# fb_relais_8_230V_85a.net
KiCad netlist of a schematic drawn in EAGLE
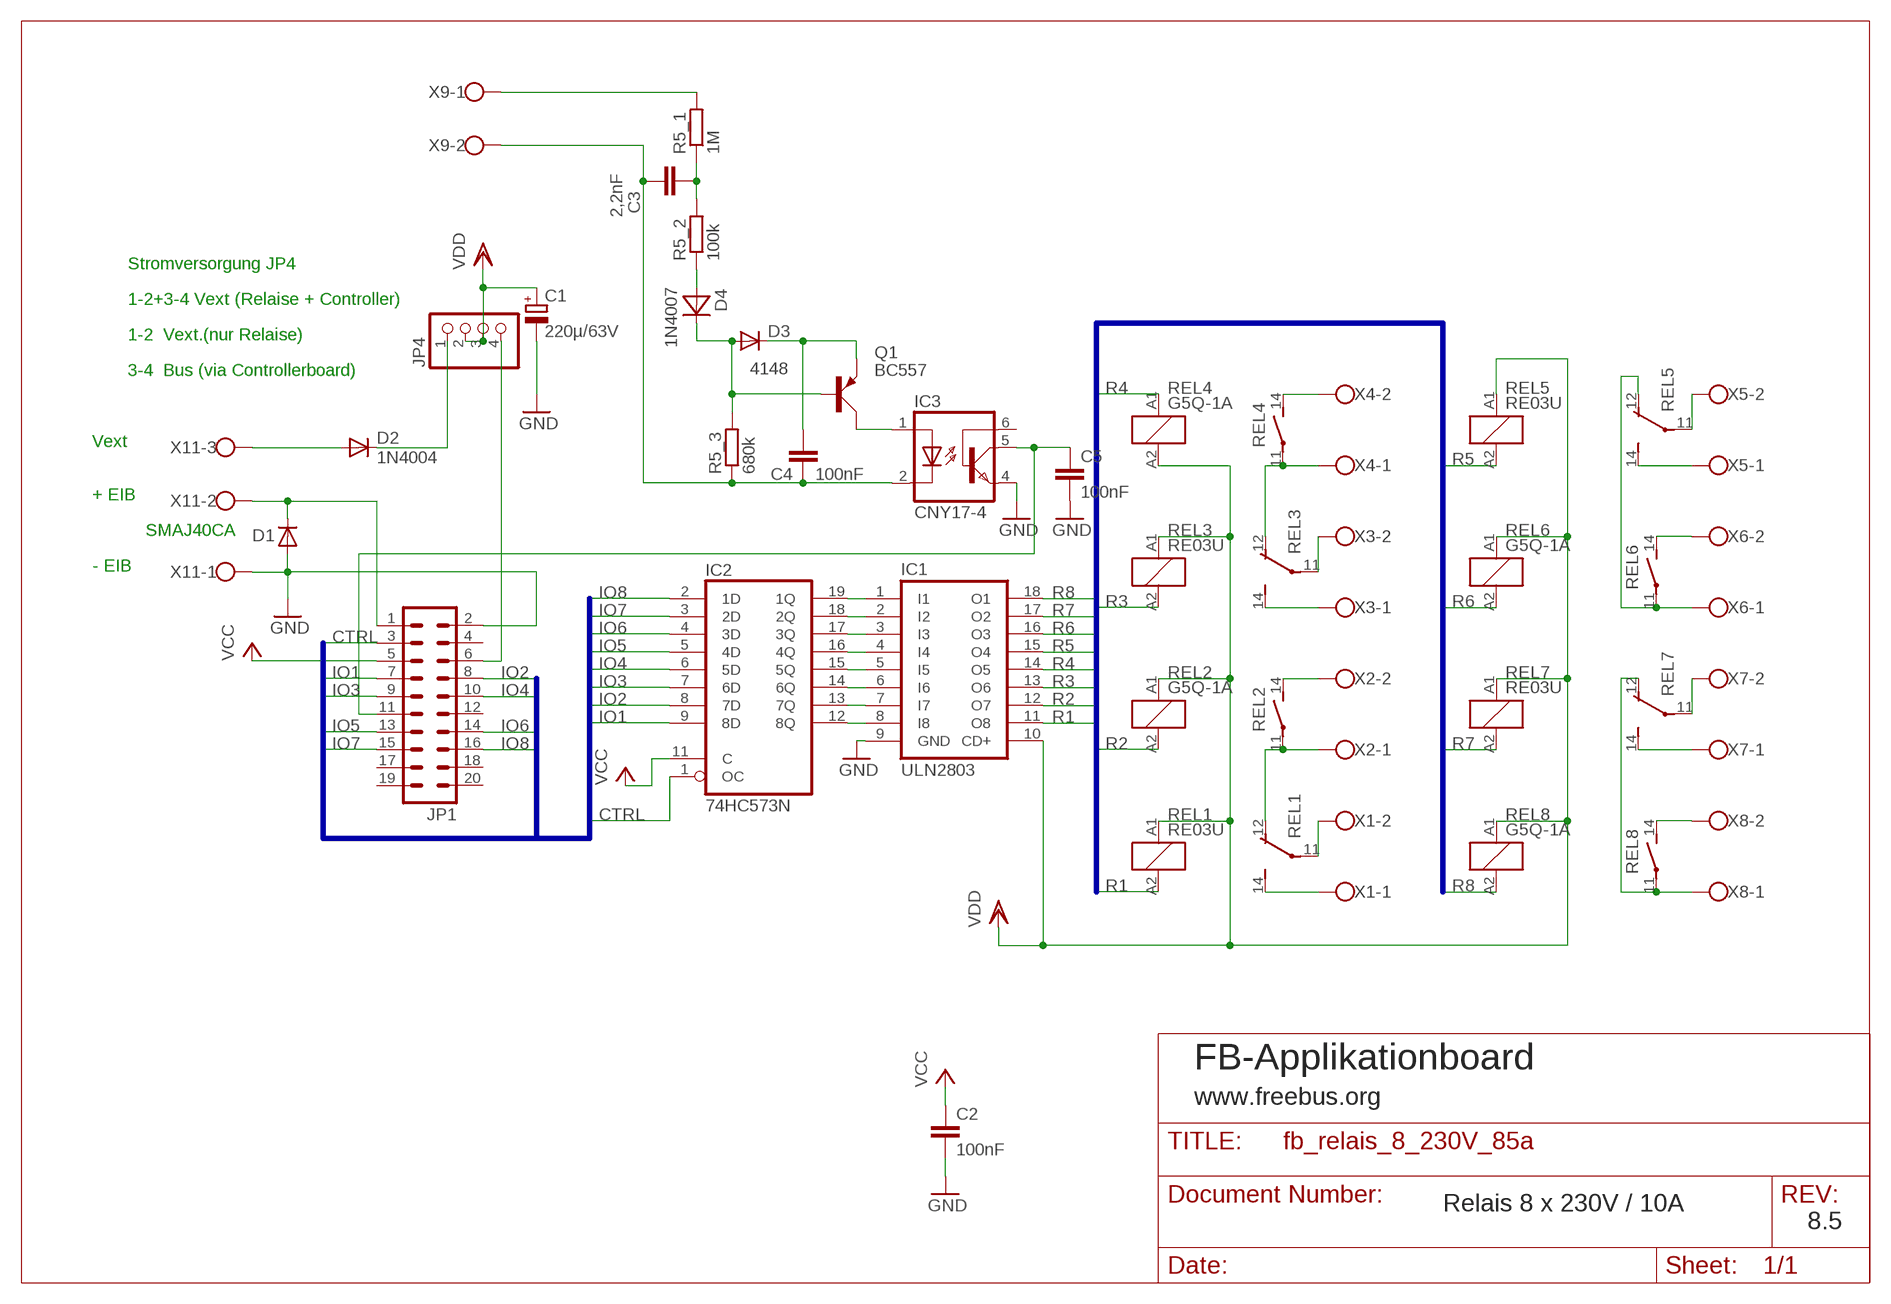
[diagram p0: schematic, sheet 1]

(export (version "E")
  (design (tool "Eeschema 10.0.6"))
  (components
    (comp (ref "C1")
      (value "220µ/63V")
      (footprint "eagle-import:E5-10,5")
      (libsource (lib "eagle-import") (part "CPOL-EUE5-10.5"))
    )
    (comp (ref "C2")
      (value "100nF")
      (footprint "eagle-import:C050-024X044")
      (libsource (lib "eagle-import") (part "C-EU050-024X044"))
    )
    (comp (ref "C3")
      (value "2,2nF")
      (footprint "eagle-import:C102-043X133")
      (libsource (lib "eagle-import") (part "C-EU102-043X133"))
    )
    (comp (ref "C4")
      (value "100nF")
      (footprint "eagle-import:C050-024X044")
      (libsource (lib "eagle-import") (part "C-EU050-024X044"))
    )
    (comp (ref "C5")
      (value "100nF")
      (footprint "eagle-import:C050-024X044")
      (libsource (lib "eagle-import") (part "C-EU050-024X044"))
    )
    (comp (ref "D1")
      (value "D-SMB")
      (footprint "eagle-import:SMB")
      (libsource (lib "eagle-import") (part "D-SMB"))
    )
    (comp (ref "D2")
      (value "1N4004")
      (footprint "eagle-import:DO41-10")
      (libsource (lib "eagle-import") (part "1N4004"))
    )
    (comp (ref "D3")
      (value "4148")
      (footprint "eagle-import:D-2.5")
      (libsource (lib "eagle-import") (part "1N41481448V"))
    )
    (comp (ref "D4")
      (value "1N4007")
      (footprint "eagle-import:DO41-7")
      (libsource (lib "eagle-import") (part "1N4007"))
    )
    (comp (ref "IC1")
      (value "ULN2803")
      (footprint "eagle-import:DIL18")
      (libsource (lib "eagle-import") (part "ULN2803A"))
    )
    (comp (ref "IC2")
      (value "74HC573N")
      (footprint "eagle-import:DIL20")
      (libsource (lib "eagle-import") (part "74573NHC"))
    )
    (comp (ref "IC3")
      (value "CNY17-4")
      (footprint "eagle-import:DIL06")
      (libsource (lib "eagle-import") (part "CNY17"))
    )
    (comp (ref "JP1")
      (value "ML20")
      (footprint "eagle-import:ML20")
      (libsource (lib "eagle-import") (part "ML20"))
    )
    (comp (ref "JP4")
      (value "PINHD-1X4")
      (footprint "eagle-import:1X04")
      (libsource (lib "eagle-import") (part "PINHD-1X4"))
    )
    (comp (ref "Q1")
      (value "BC557")
      (footprint "eagle-import:SOT54A")
      (libsource (lib "eagle-import") (part "BC557"))
    )
    (comp (ref "R5_1")
      (value "1M")
      (footprint "eagle-import:0207_7")
      (libsource (lib "eagle-import") (part "R-EU_0207/7"))
    )
    (comp (ref "R5_2")
      (value "100k")
      (footprint "eagle-import:0207_7")
      (libsource (lib "eagle-import") (part "R-EU_0207/7"))
    )
    (comp (ref "R5_3")
      (value "680k")
      (footprint "eagle-import:0207_7")
      (libsource (lib "eagle-import") (part "R-EU_0207/7"))
    )
    (comp (ref "REL1")
      (value "RE03U")
      (footprint "eagle-import:G5Q_1_EU")
      (libsource (lib "eagle-import") (part "RE03U"))
    )
    (comp (ref "REL2")
      (value "G5Q-1A")
      (footprint "eagle-import:RE-SCHRACK")
      (libsource (lib "eagle-import") (part "RE030024"))
    )
    (comp (ref "REL3")
      (value "RE03U")
      (footprint "eagle-import:G5Q_1_EU")
      (libsource (lib "eagle-import") (part "RE03U"))
    )
    (comp (ref "REL4")
      (value "G5Q-1A")
      (footprint "eagle-import:RE-SCHRACK")
      (libsource (lib "eagle-import") (part "RE030024"))
    )
    (comp (ref "REL5")
      (value "RE03U")
      (footprint "eagle-import:G5Q_1_EU")
      (libsource (lib "eagle-import") (part "RE03U"))
    )
    (comp (ref "REL6")
      (value "G5Q-1A")
      (footprint "eagle-import:RE-SCHRACK")
      (libsource (lib "eagle-import") (part "RE030024"))
    )
    (comp (ref "REL7")
      (value "RE03U")
      (footprint "eagle-import:G5Q_1_EU")
      (libsource (lib "eagle-import") (part "RE03U"))
    )
    (comp (ref "REL8")
      (value "G5Q-1A")
      (footprint "eagle-import:RE-SCHRACK")
      (libsource (lib "eagle-import") (part "RE030024"))
    )
    (comp (ref "X1")
      (value "W237-102")
      (footprint "eagle-import:W237-102")
      (libsource (lib "eagle-import") (part "W237-102"))
    )
    (comp (ref "X2")
      (value "W237-102")
      (footprint "eagle-import:W237-102")
      (libsource (lib "eagle-import") (part "W237-102"))
    )
    (comp (ref "X3")
      (value "W237-102")
      (footprint "eagle-import:W237-102")
      (libsource (lib "eagle-import") (part "W237-102"))
    )
    (comp (ref "X4")
      (value "W237-102")
      (footprint "eagle-import:W237-102")
      (libsource (lib "eagle-import") (part "W237-102"))
    )
    (comp (ref "X5")
      (value "W237-102")
      (footprint "eagle-import:W237-102")
      (libsource (lib "eagle-import") (part "W237-102"))
    )
    (comp (ref "X6")
      (value "W237-102")
      (footprint "eagle-import:W237-102")
      (libsource (lib "eagle-import") (part "W237-102"))
    )
    (comp (ref "X7")
      (value "W237-102")
      (footprint "eagle-import:W237-102")
      (libsource (lib "eagle-import") (part "W237-102"))
    )
    (comp (ref "X8")
      (value "W237-102")
      (footprint "eagle-import:W237-102")
      (libsource (lib "eagle-import") (part "W237-102"))
    )
    (comp (ref "X9")
      (value "W237-102")
      (footprint "eagle-import:W237-102")
      (libsource (lib "eagle-import") (part "W237-102"))
    )
    (comp (ref "X11")
      (value "W237-3E")
      (footprint "eagle-import:W237-3E")
      (libsource (lib "eagle-import") (part "W237-3E"))
    )
  )
  (nets
    (net (code "1") (name "/CTRL") (class "Default")
      (node (ref "IC2") (pin "1") (pinfunction "OC_1") (pintype "input"))
      (node (ref "JP1") (pin "3") (pinfunction "3_3") (pintype "passive"))
    )
    (net (code "2") (name "/IO1") (class "Default")
      (node (ref "IC2") (pin "9") (pinfunction "8D_9") (pintype "input"))
      (node (ref "JP1") (pin "7") (pinfunction "7_7") (pintype "passive"))
    )
    (net (code "3") (name "/IO2") (class "Default")
      (node (ref "IC2") (pin "8") (pinfunction "7D_8") (pintype "input"))
      (node (ref "JP1") (pin "8") (pinfunction "8_8") (pintype "passive"))
    )
    (net (code "4") (name "/IO3") (class "Default")
      (node (ref "IC2") (pin "7") (pinfunction "6D_7") (pintype "input"))
      (node (ref "JP1") (pin "9") (pinfunction "9_9") (pintype "passive"))
    )
    (net (code "5") (name "/IO4") (class "Default")
      (node (ref "IC2") (pin "6") (pinfunction "5D_6") (pintype "input"))
      (node (ref "JP1") (pin "10") (pinfunction "10_10") (pintype "passive"))
    )
    (net (code "6") (name "/IO5") (class "Default")
      (node (ref "IC2") (pin "5") (pinfunction "4D_5") (pintype "input"))
      (node (ref "JP1") (pin "13") (pinfunction "13_13") (pintype "passive"))
    )
    (net (code "7") (name "/IO6") (class "Default")
      (node (ref "IC2") (pin "4") (pinfunction "3D_4") (pintype "input"))
      (node (ref "JP1") (pin "14") (pinfunction "14_14") (pintype "passive"))
    )
    (net (code "8") (name "/IO7") (class "Default")
      (node (ref "IC2") (pin "3") (pinfunction "2D_3") (pintype "input"))
      (node (ref "JP1") (pin "15") (pinfunction "15_15") (pintype "passive"))
    )
    (net (code "9") (name "/IO8") (class "Default")
      (node (ref "IC2") (pin "2") (pinfunction "1D_2") (pintype "input"))
      (node (ref "JP1") (pin "16") (pinfunction "16_16") (pintype "passive"))
    )
    (net (code "10") (name "/R1") (class "Default")
      (node (ref "IC1") (pin "11") (pinfunction "O8_11") (pintype "open_collector"))
      (node (ref "REL1") (pin "A2") (pinfunction "2_A2") (pintype "passive"))
    )
    (net (code "11") (name "/R2") (class "Default")
      (node (ref "IC1") (pin "12") (pinfunction "O7_12") (pintype "open_collector"))
      (node (ref "REL2") (pin "A2") (pinfunction "2_A2") (pintype "passive"))
    )
    (net (code "12") (name "/R3") (class "Default")
      (node (ref "IC1") (pin "13") (pinfunction "O6_13") (pintype "open_collector"))
      (node (ref "REL3") (pin "A2") (pinfunction "2_A2") (pintype "passive"))
    )
    (net (code "13") (name "/R4") (class "Default")
      (node (ref "IC1") (pin "14") (pinfunction "O5_14") (pintype "open_collector"))
      (node (ref "REL4") (pin "A1") (pinfunction "1_A1") (pintype "passive"))
    )
    (net (code "14") (name "/R5") (class "Default")
      (node (ref "IC1") (pin "15") (pinfunction "O4_15") (pintype "open_collector"))
      (node (ref "REL5") (pin "A2") (pinfunction "2_A2") (pintype "passive"))
    )
    (net (code "15") (name "/R6") (class "Default")
      (node (ref "IC1") (pin "16") (pinfunction "O3_16") (pintype "open_collector"))
      (node (ref "REL6") (pin "A2") (pinfunction "2_A2") (pintype "passive"))
    )
    (net (code "16") (name "/R7") (class "Default")
      (node (ref "IC1") (pin "17") (pinfunction "O2_17") (pintype "open_collector"))
      (node (ref "REL7") (pin "A2") (pinfunction "2_A2") (pintype "passive"))
    )
    (net (code "17") (name "/R8") (class "Default")
      (node (ref "IC1") (pin "18") (pinfunction "O1_18") (pintype "open_collector"))
      (node (ref "REL8") (pin "A2") (pinfunction "2_A2") (pintype "passive"))
    )
    (net (code "18") (name "GND") (class "Default")
      (node (ref "C1") (pin "-") (pinfunction "-_-") (pintype "passive"))
      (node (ref "C2") (pin "2") (pinfunction "2_2") (pintype "passive"))
      (node (ref "C5") (pin "2") (pinfunction "2_2") (pintype "passive"))
      (node (ref "D1") (pin "2") (pinfunction "A_2") (pintype "passive"))
      (node (ref "IC1") (pin "9") (pinfunction "GND_9") (pintype "power_in"))
      (node (ref "IC3") (pin "4") (pinfunction "EMI_4") (pintype "passive"))
      (node (ref "JP1") (pin "2") (pinfunction "2_2") (pintype "passive"))
      (node (ref "X11") (pin "1") (pinfunction "KL_1") (pintype "passive"))
    )
    (net (code "19") (name "Net-(C3-Pad1)") (class "Default")
      (node (ref "C3") (pin "1") (pinfunction "1_1") (pintype "passive"))
      (node (ref "R5_1") (pin "1") (pinfunction "1_1") (pintype "passive"))
      (node (ref "R5_2") (pin "2") (pinfunction "2_2") (pintype "passive"))
    )
    (net (code "20") (name "Net-(C4-Pad2)") (class "Default")
      (node (ref "C4") (pin "2") (pinfunction "2_2") (pintype "passive"))
      (node (ref "D3") (pin "C") (pinfunction "C_C") (pintype "passive"))
      (node (ref "Q1") (pin "E") (pinfunction "E_E") (pintype "passive"))
    )
    (net (code "21") (name "Net-(D1-C)") (class "Default")
      (node (ref "D1") (pin "1") (pinfunction "C_1") (pintype "passive"))
      (node (ref "JP1") (pin "1") (pinfunction "1_1") (pintype "passive"))
      (node (ref "X11") (pin "2") (pinfunction "KL_2") (pintype "passive"))
    )
    (net (code "22") (name "Net-(D2-PadC)") (class "Default")
      (node (ref "D2") (pin "C") (pinfunction "C_C") (pintype "passive"))
      (node (ref "JP4") (pin "1") (pinfunction "1_1") (pintype "passive"))
    )
    (net (code "23") (name "Net-(D3-PadA)") (class "Default")
      (node (ref "D3") (pin "A") (pinfunction "A_A") (pintype "passive"))
      (node (ref "D4") (pin "C") (pinfunction "C_C") (pintype "passive"))
      (node (ref "Q1") (pin "B") (pinfunction "B_B") (pintype "passive"))
      (node (ref "R5_3") (pin "2") (pinfunction "2_2") (pintype "passive"))
    )
    (net (code "24") (name "Net-(D4-PadA)") (class "Default")
      (node (ref "D4") (pin "A") (pinfunction "A_A") (pintype "passive"))
      (node (ref "R5_2") (pin "1") (pinfunction "1_1") (pintype "passive"))
    )
    (net (code "25") (name "Net-(IC1-I1)") (class "Default")
      (node (ref "IC1") (pin "1") (pinfunction "I1_1") (pintype "input"))
      (node (ref "IC2") (pin "19") (pinfunction "1Q_19") (pintype "tri_state"))
    )
    (net (code "26") (name "Net-(IC1-I2)") (class "Default")
      (node (ref "IC1") (pin "2") (pinfunction "I2_2") (pintype "input"))
      (node (ref "IC2") (pin "18") (pinfunction "2Q_18") (pintype "tri_state"))
    )
    (net (code "27") (name "Net-(IC1-I3)") (class "Default")
      (node (ref "IC1") (pin "3") (pinfunction "I3_3") (pintype "input"))
      (node (ref "IC2") (pin "17") (pinfunction "3Q_17") (pintype "tri_state"))
    )
    (net (code "28") (name "Net-(IC1-I4)") (class "Default")
      (node (ref "IC1") (pin "4") (pinfunction "I4_4") (pintype "input"))
      (node (ref "IC2") (pin "16") (pinfunction "4Q_16") (pintype "tri_state"))
    )
    (net (code "29") (name "Net-(IC1-I5)") (class "Default")
      (node (ref "IC1") (pin "5") (pinfunction "I5_5") (pintype "input"))
      (node (ref "IC2") (pin "15") (pinfunction "5Q_15") (pintype "tri_state"))
    )
    (net (code "30") (name "Net-(IC1-I6)") (class "Default")
      (node (ref "IC1") (pin "6") (pinfunction "I6_6") (pintype "input"))
      (node (ref "IC2") (pin "14") (pinfunction "6Q_14") (pintype "tri_state"))
    )
    (net (code "31") (name "Net-(IC1-I7)") (class "Default")
      (node (ref "IC1") (pin "7") (pinfunction "I7_7") (pintype "input"))
      (node (ref "IC2") (pin "13") (pinfunction "7Q_13") (pintype "tri_state"))
    )
    (net (code "32") (name "Net-(IC1-I8)") (class "Default")
      (node (ref "IC1") (pin "8") (pinfunction "I8_8") (pintype "input"))
      (node (ref "IC2") (pin "12") (pinfunction "8Q_12") (pintype "tri_state"))
    )
    (net (code "33") (name "Net-(IC3-A)") (class "Default")
      (node (ref "IC3") (pin "1") (pinfunction "A_1") (pintype "passive"))
      (node (ref "Q1") (pin "C") (pinfunction "C_C") (pintype "passive"))
    )
    (net (code "34") (name "Net-(IC3-C)") (class "Default")
      (node (ref "C3") (pin "2") (pinfunction "2_2") (pintype "passive"))
      (node (ref "C4") (pin "1") (pinfunction "1_1") (pintype "passive"))
      (node (ref "IC3") (pin "2") (pinfunction "C_2") (pintype "passive"))
      (node (ref "R5_3") (pin "1") (pinfunction "1_1") (pintype "passive"))
      (node (ref "X9") (pin "2") (pinfunction "KL_2") (pintype "passive"))
    )
    (net (code "35") (name "Net-(IC3-COL)") (class "Default")
      (node (ref "C5") (pin "1") (pinfunction "1_1") (pintype "passive"))
      (node (ref "IC3") (pin "5") (pinfunction "COL_5") (pintype "passive"))
      (node (ref "JP1") (pin "11") (pinfunction "11_11") (pintype "passive"))
    )
    (net (code "36") (name "Net-(JP1-Pad6)") (class "Default")
      (node (ref "JP1") (pin "6") (pinfunction "6_6") (pintype "passive"))
      (node (ref "JP4") (pin "4") (pinfunction "4_4") (pintype "passive"))
    )
    (net (code "37") (name "Net-(REL1A-O)") (class "Default")
      (node (ref "REL1") (pin "12") (pinfunction "O_12") (pintype "passive"))
      (node (ref "REL2") (pin "11") (pinfunction "P_11") (pintype "passive"))
      (node (ref "X2") (pin "1") (pinfunction "KL_1") (pintype "passive"))
    )
    (net (code "38") (name "Net-(REL1A-P)") (class "Default")
      (node (ref "REL1") (pin "11") (pinfunction "P_11") (pintype "passive"))
      (node (ref "X1") (pin "2") (pinfunction "KL_2") (pintype "passive"))
    )
    (net (code "39") (name "Net-(REL1A-S)") (class "Default")
      (node (ref "REL1") (pin "14") (pinfunction "S_14") (pintype "passive"))
      (node (ref "X1") (pin "1") (pinfunction "KL_1") (pintype "passive"))
    )
    (net (code "40") (name "Net-(REL2B-S)") (class "Default")
      (node (ref "REL2") (pin "14") (pinfunction "S_14") (pintype "passive"))
      (node (ref "X2") (pin "2") (pinfunction "KL_2") (pintype "passive"))
    )
    (net (code "41") (name "Net-(REL3A-O)") (class "Default")
      (node (ref "REL3") (pin "12") (pinfunction "O_12") (pintype "passive"))
      (node (ref "REL4") (pin "11") (pinfunction "P_11") (pintype "passive"))
      (node (ref "X4") (pin "1") (pinfunction "KL_1") (pintype "passive"))
    )
    (net (code "42") (name "Net-(REL3A-P)") (class "Default")
      (node (ref "REL3") (pin "11") (pinfunction "P_11") (pintype "passive"))
      (node (ref "X3") (pin "2") (pinfunction "KL_2") (pintype "passive"))
    )
    (net (code "43") (name "Net-(REL3A-S)") (class "Default")
      (node (ref "REL3") (pin "14") (pinfunction "S_14") (pintype "passive"))
      (node (ref "X3") (pin "1") (pinfunction "KL_1") (pintype "passive"))
    )
    (net (code "44") (name "Net-(REL4B-S)") (class "Default")
      (node (ref "REL4") (pin "14") (pinfunction "S_14") (pintype "passive"))
      (node (ref "X4") (pin "2") (pinfunction "KL_2") (pintype "passive"))
    )
    (net (code "45") (name "Net-(REL5A-O)") (class "Default")
      (node (ref "REL5") (pin "12") (pinfunction "O_12") (pintype "passive"))
      (node (ref "REL6") (pin "11") (pinfunction "P_11") (pintype "passive"))
      (node (ref "X6") (pin "1") (pinfunction "KL_1") (pintype "passive"))
    )
    (net (code "46") (name "Net-(REL5A-P)") (class "Default")
      (node (ref "REL5") (pin "11") (pinfunction "P_11") (pintype "passive"))
      (node (ref "X5") (pin "2") (pinfunction "KL_2") (pintype "passive"))
    )
    (net (code "47") (name "Net-(REL5A-S)") (class "Default")
      (node (ref "REL5") (pin "14") (pinfunction "S_14") (pintype "passive"))
      (node (ref "X5") (pin "1") (pinfunction "KL_1") (pintype "passive"))
    )
    (net (code "48") (name "Net-(REL6B-S)") (class "Default")
      (node (ref "REL6") (pin "14") (pinfunction "S_14") (pintype "passive"))
      (node (ref "X6") (pin "2") (pinfunction "KL_2") (pintype "passive"))
    )
    (net (code "49") (name "Net-(REL7A-O)") (class "Default")
      (node (ref "REL7") (pin "12") (pinfunction "O_12") (pintype "passive"))
      (node (ref "REL8") (pin "11") (pinfunction "P_11") (pintype "passive"))
      (node (ref "X8") (pin "1") (pinfunction "KL_1") (pintype "passive"))
    )
    (net (code "50") (name "Net-(REL7A-P)") (class "Default")
      (node (ref "REL7") (pin "11") (pinfunction "P_11") (pintype "passive"))
      (node (ref "X7") (pin "2") (pinfunction "KL_2") (pintype "passive"))
    )
    (net (code "51") (name "Net-(REL7A-S)") (class "Default")
      (node (ref "REL7") (pin "14") (pinfunction "S_14") (pintype "passive"))
      (node (ref "X7") (pin "1") (pinfunction "KL_1") (pintype "passive"))
    )
    (net (code "52") (name "Net-(REL8B-S)") (class "Default")
      (node (ref "REL8") (pin "14") (pinfunction "S_14") (pintype "passive"))
      (node (ref "X8") (pin "2") (pinfunction "KL_2") (pintype "passive"))
    )
    (net (code "53") (name "Net-(X9A-KL)") (class "Default")
      (node (ref "R5_1") (pin "2") (pinfunction "2_2") (pintype "passive"))
      (node (ref "X9") (pin "1") (pinfunction "KL_1") (pintype "passive"))
    )
    (net (code "54") (name "Net-(X11C-KL)") (class "Default")
      (node (ref "D2") (pin "A") (pinfunction "A_A") (pintype "passive"))
      (node (ref "X11") (pin "3") (pinfunction "KL_3") (pintype "passive"))
    )
    (net (code "55") (name "VCC") (class "Default")
      (node (ref "C2") (pin "1") (pinfunction "1_1") (pintype "passive"))
      (node (ref "IC2") (pin "11") (pinfunction "C_11") (pintype "input"))
      (node (ref "JP1") (pin "5") (pinfunction "5_5") (pintype "passive"))
    )
    (net (code "56") (name "VDD") (class "Default")
      (node (ref "C1") (pin "+") (pinfunction "+_+") (pintype "passive"))
      (node (ref "IC1") (pin "10") (pinfunction "CD+_10") (pintype "passive"))
      (node (ref "JP4") (pin "2") (pinfunction "2_2") (pintype "passive"))
      (node (ref "JP4") (pin "3") (pinfunction "3_3") (pintype "passive"))
      (node (ref "REL1") (pin "A1") (pinfunction "1_A1") (pintype "passive"))
      (node (ref "REL2") (pin "A1") (pinfunction "1_A1") (pintype "passive"))
      (node (ref "REL3") (pin "A1") (pinfunction "1_A1") (pintype "passive"))
      (node (ref "REL4") (pin "A2") (pinfunction "2_A2") (pintype "passive"))
      (node (ref "REL5") (pin "A1") (pinfunction "1_A1") (pintype "passive"))
      (node (ref "REL6") (pin "A1") (pinfunction "1_A1") (pintype "passive"))
      (node (ref "REL7") (pin "A1") (pinfunction "1_A1") (pintype "passive"))
      (node (ref "REL8") (pin "A1") (pinfunction "1_A1") (pintype "passive"))
    )
    (net (code "57") (name "unconnected-(IC3-BAS-Pad6)") (class "Default")
      (node (ref "IC3") (pin "6") (pinfunction "BAS_6") (pintype "passive"))
    )
    (net (code "58") (name "unconnected-(JP1-Pad4)") (class "Default")
      (node (ref "JP1") (pin "4") (pinfunction "4_4") (pintype "passive"))
    )
    (net (code "59") (name "unconnected-(JP1-Pad12)") (class "Default")
      (node (ref "JP1") (pin "12") (pinfunction "12_12") (pintype "passive"))
    )
    (net (code "60") (name "unconnected-(JP1-Pad17)") (class "Default")
      (node (ref "JP1") (pin "17") (pinfunction "17_17") (pintype "passive"))
    )
    (net (code "61") (name "unconnected-(JP1-Pad18)") (class "Default")
      (node (ref "JP1") (pin "18") (pinfunction "18_18") (pintype "passive"))
    )
    (net (code "62") (name "unconnected-(JP1-Pad19)") (class "Default")
      (node (ref "JP1") (pin "19") (pinfunction "19_19") (pintype "passive"))
    )
    (net (code "63") (name "unconnected-(JP1-Pad20)") (class "Default")
      (node (ref "JP1") (pin "20") (pinfunction "20_20") (pintype "passive"))
    )
  )
)
